# Hardware5button.net
KiCad netlist of a schematic drawn in Altium Designer
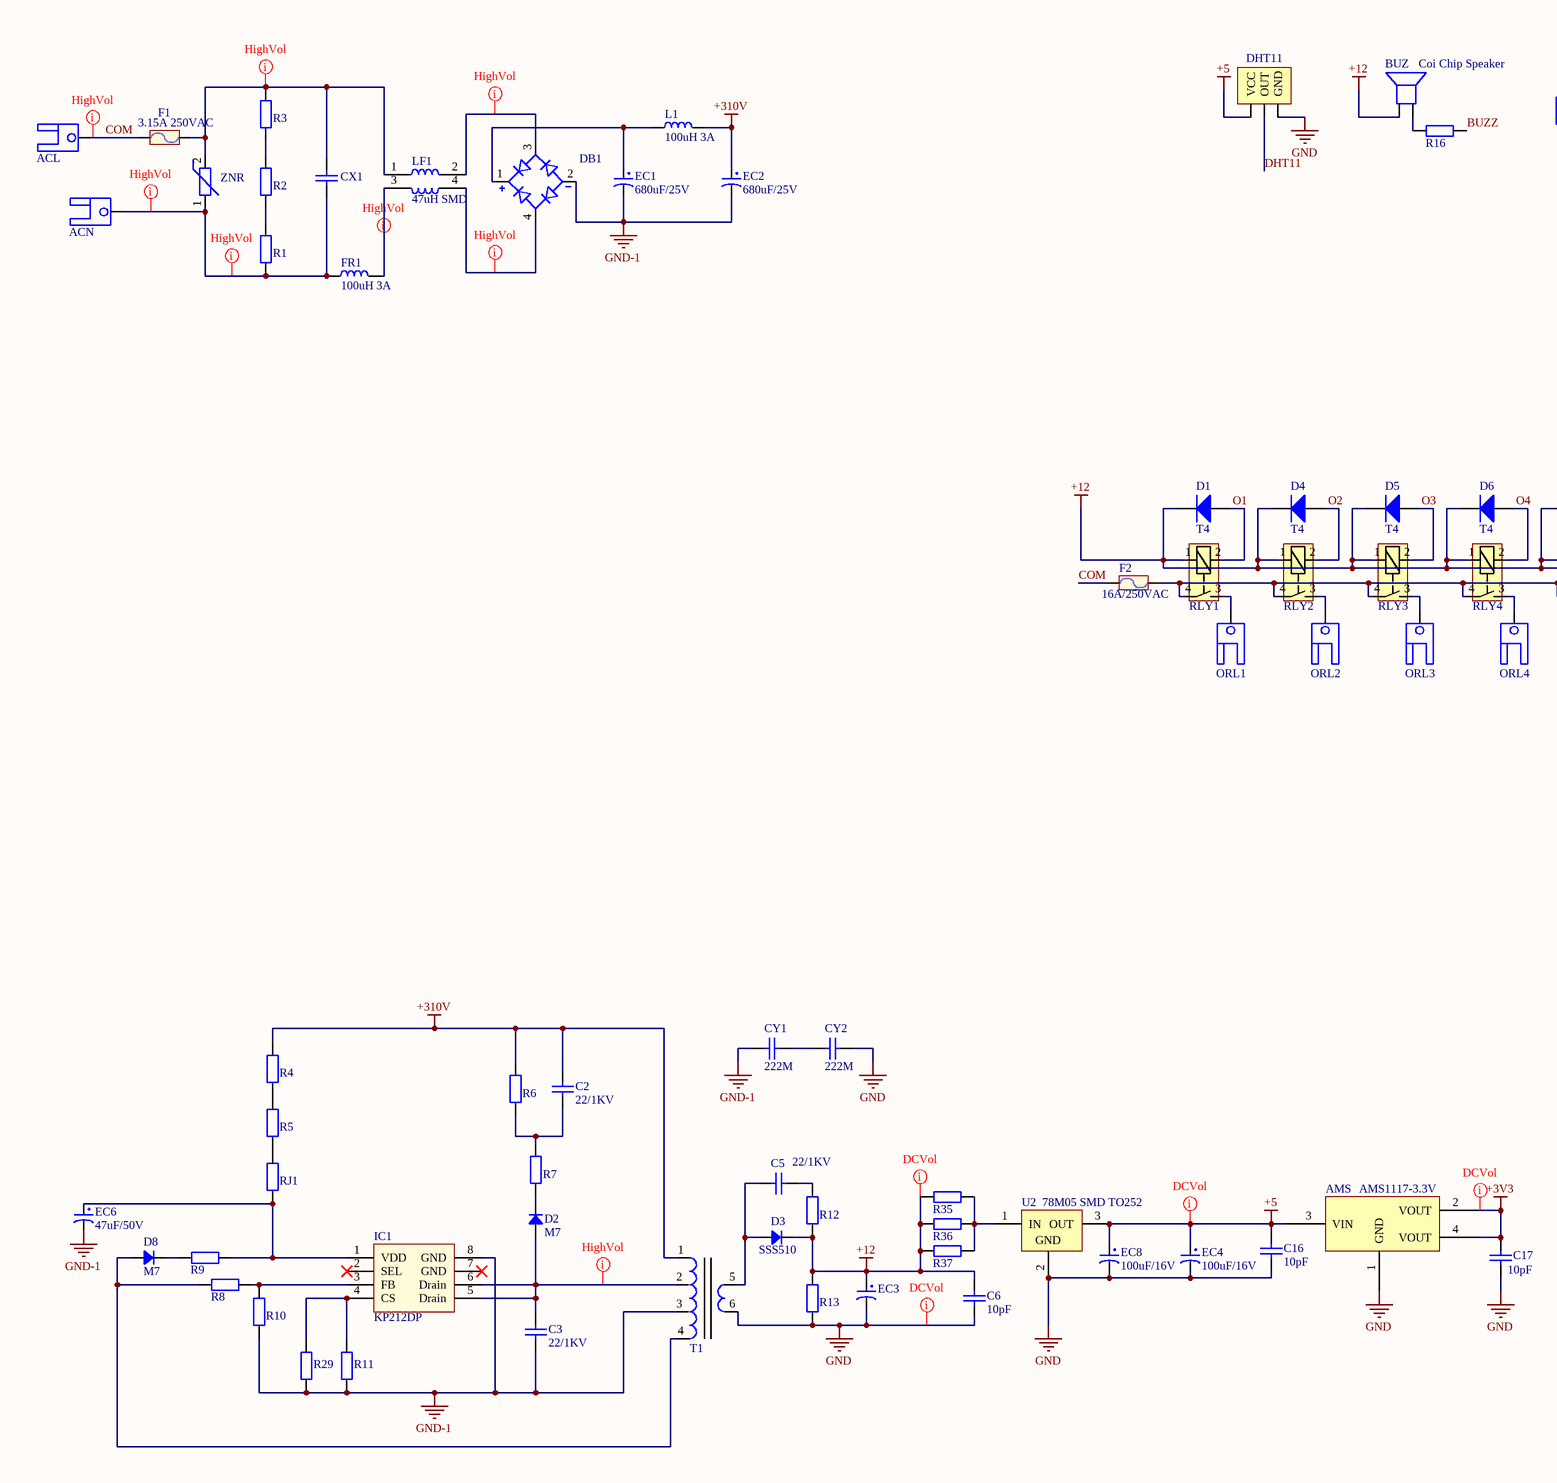
[diagram p0: Hardware5button.SchDoc, left]
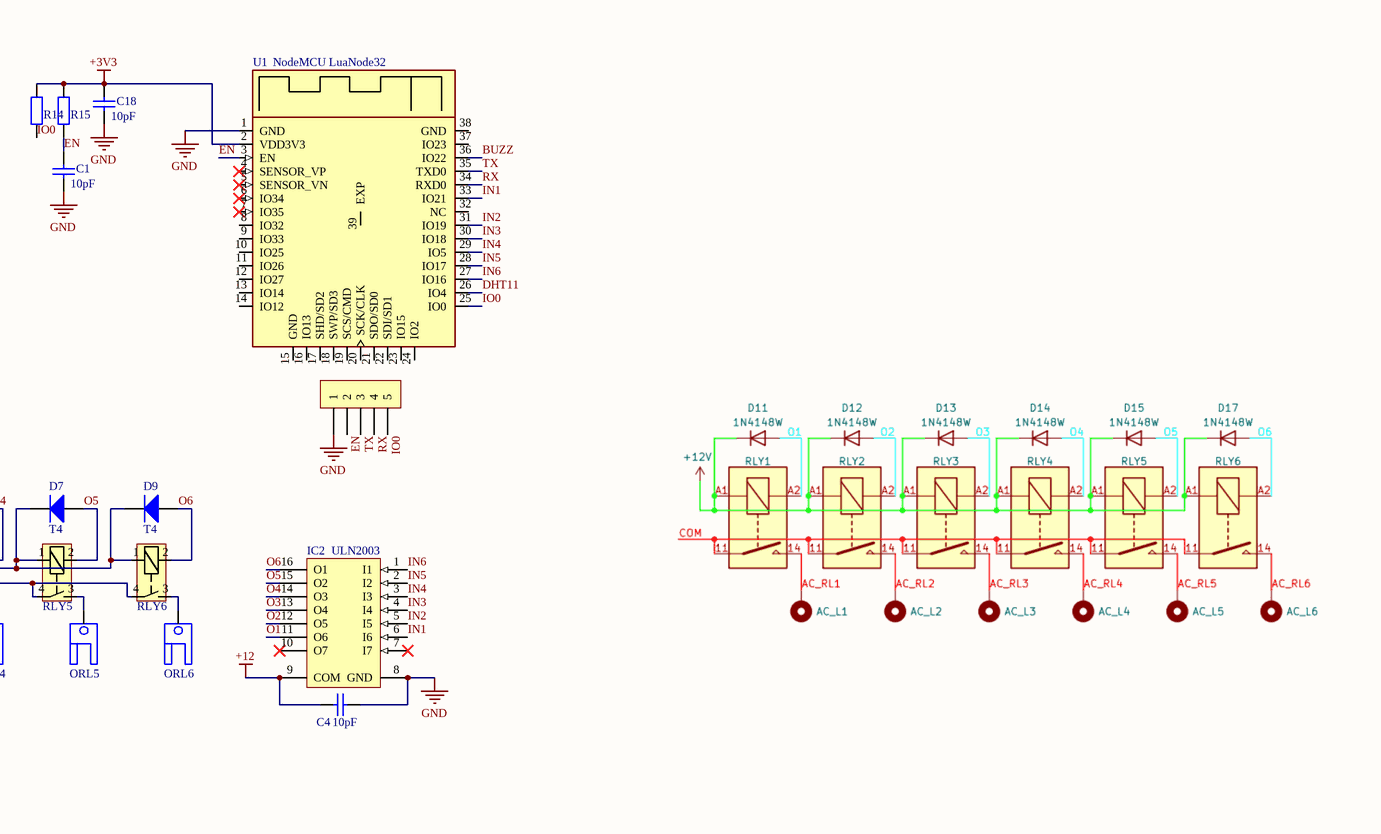
[diagram p1: Hardware5button.SchDoc, right]

(export (version "E")
  (design (tool "Eeschema 10.0.6"))
  (components
    (comp (ref "ACL")
      (value "1217861-1")
      (footprint "CON1_P192_70D137_TH_ST")
      (description "1 Pins, 1 Row 256mil Pitch, Straight, Male")
      (fields
        (field (name "MANUFACTURER") "TE Connectivity")
        (field (name "MATING PART NUMBER") "2-520183-2")
      )
      (libsource (lib "SF16_POWER") (part "CON-PLG-SPADE_1X1-256-ST-TH"))
    )
    (comp (ref "ACN")
      (value "1217861-1")
      (footprint "CON1_P192_70D137_TH_ST")
      (description "1 Pins, 1 Row 256mil Pitch, Straight, Male")
      (fields
        (field (name "MANUFACTURER") "TE Connectivity")
        (field (name "MATING PART NUMBER") "2-520183-2")
      )
      (libsource (lib "SF16_POWER") (part "CON-PLG-SPADE_1X1-256-ST-TH"))
    )
    (comp (ref "AMS")
      (value "AMS1117-3.3V")
      (footprint "SOT223")
      (description "Dán")
      (libsource (lib "SF16_POWER") (part "AMS1117 SMD"))
    )
    (comp (ref "BUZ")
      (value "Coi Chip Speaker")
      (footprint "Coi 14mm")
      (description "Cắm")
      (libsource (lib "SF16_POWER") (part "Coi 14mm"))
    )
    (comp (ref "C1")
      (value "10pF")
      (footprint "tu 0805")
      (description "Dán")
      (libsource (lib "SF16_POWER") (part "Tu 0805 10pF 50V 10%"))
    )
    (comp (ref "C2")
      (value "22/1KV")
      (footprint "TU GOM CAO AP")
      (description "Cắm")
      (libsource (lib "SF16_POWER") (part "Tu gom CAO AP"))
    )
    (comp (ref "C3")
      (value "22/1KV")
      (footprint "TU GOM CAO AP")
      (description "Cắm")
      (libsource (lib "SF16_POWER") (part "Tu gom CAO AP"))
    )
    (comp (ref "C4")
      (value "10pF")
      (footprint "tu 0805")
      (description "Dán")
      (libsource (lib "SF16_POWER") (part "Tu 0805 10pF 50V 10%"))
    )
    (comp (ref "C5")
      (value "22/1KV")
      (footprint "TU GOM CAO AP")
      (description "Cắm")
      (libsource (lib "SF16_POWER") (part "Tu gom CAO AP"))
    )
    (comp (ref "C6")
      (value "10pF")
      (footprint "tu 0805")
      (description "Dán")
      (libsource (lib "SF16_POWER") (part "Tu 0805 10pF 50V 10%"))
    )
    (comp (ref "C16")
      (value "10pF")
      (footprint "tu 0805")
      (description "Dán")
      (libsource (lib "SF16_POWER") (part "Tu 0805 10pF 50V 10%"))
    )
    (comp (ref "C17")
      (value "10pF")
      (footprint "tu 0805")
      (description "Dán")
      (libsource (lib "SF16_POWER") (part "Tu 0805 10pF 50V 10%"))
    )
    (comp (ref "C18")
      (value "10pF")
      (footprint "tu 0805")
      (description "Dán")
      (libsource (lib "SF16_POWER") (part "Tu 0805 10pF 50V 10%"))
    )
    (comp (ref "CX1")
      (value "0.1")
      (footprint "Tu vuong 10mm")
      (description "Cắm")
      (libsource (lib "SF16_POWER") (part "Tu MKP X2 0.1uF 275VAC 10MM"))
    )
    (comp (ref "CY1")
      (value "222M")
      (footprint "TU GOM CAO AP 222M")
      (description "Cắm")
      (libsource (lib "SF16_POWER") (part "Tu gom CAO AP 222M"))
    )
    (comp (ref "CY2")
      (value "222M")
      (footprint "TU GOM CAO AP 222M")
      (description "Cắm")
      (libsource (lib "SF16_POWER") (part "Tu gom CAO AP 222M"))
    )
    (comp (ref "D1")
      (value "T4")
      (footprint "DIODE SOD-123")
      (description "Dán")
      (libsource (lib "SF16_POWER") (part "Diode S4"))
    )
    (comp (ref "D2")
      (value "M7")
      (footprint "DIODE SMA")
      (description "Dán")
      (libsource (lib "SF16_POWER") (part "Diode M7 1N4007 SMD 1A 1000V"))
    )
    (comp (ref "D3")
      (value "SSS510")
      (footprint "DIODE SMA")
      (description "Dán")
      (libsource (lib "SF16_POWER") (part "Diode M7 1N4007 SMD 1A 1000V"))
    )
    (comp (ref "D4")
      (value "T4")
      (footprint "DIODE SOD-123")
      (description "Dán")
      (libsource (lib "SF16_POWER") (part "Diode S4"))
    )
    (comp (ref "D5")
      (value "T4")
      (footprint "DIODE SOD-123")
      (description "Dán")
      (libsource (lib "SF16_POWER") (part "Diode S4"))
    )
    (comp (ref "D6")
      (value "T4")
      (footprint "DIODE SOD-123")
      (description "Dán")
      (libsource (lib "SF16_POWER") (part "Diode S4"))
    )
    (comp (ref "D7")
      (value "T4")
      (footprint "DIODE SOD-123")
      (description "Dán")
      (libsource (lib "SF16_POWER") (part "Diode S4"))
    )
    (comp (ref "D8")
      (value "M7")
      (footprint "DIODE SMA")
      (description "Dán")
      (libsource (lib "SF16_POWER") (part "Diode M7 1N4007 SMD 1A 1000V"))
    )
    (comp (ref "D9")
      (value "T4")
      (footprint "DIODE SOD-123")
      (description "Dán")
      (libsource (lib "SF16_POWER") (part "Diode S4"))
    )
    (comp (ref "DB1")
      (value "MLB10S")
      (footprint "MBLS-1")
      (description "DÁN")
      (libsource (lib "SF16_POWER") (part "diode cau MLB10S"))
    )
    (comp (ref "DHT11")
      (value "1x3 2.54")
      (footprint "DHT11")
      (description "Cắm")
      (libsource (lib "SF16_POWER") (part "DHT11 Module"))
    )
    (comp (ref "EC1")
      (value "680uF/25V")
      (footprint "tu hoa 10mm")
      (description "Cắm")
      (libsource (lib "SF16_POWER") (part "Tu Hoa 6.8uF 400V 10x17"))
    )
    (comp (ref "EC2")
      (value "680uF/25V")
      (footprint "tu hoa 10mm")
      (description "Cắm")
      (libsource (lib "SF16_POWER") (part "Tu Hoa 6.8uF 400V 10x17"))
    )
    (comp (ref "EC3")
      (value "10UF/400V")
      (footprint "tu hoa 10mm")
      (description "Cắm")
      (libsource (lib "SF16_POWER") (part "Tu Hoa 1000uF 10V 10x12"))
    )
    (comp (ref "EC4")
      (value "100uF/16V")
      (footprint "tu hoa 5mm")
      (description "Cắm")
      (libsource (lib "SF16_POWER") (part "Tu Hoa 330uF 10V 6x11"))
    )
    (comp (ref "EC6")
      (value "47uF/50V")
      (footprint "tu hoa 5mm")
      (description "Cắm")
      (libsource (lib "SF16_POWER") (part "Tu Hoa 47uF 16V 5x10"))
    )
    (comp (ref "EC8")
      (value "100uF/16V")
      (footprint "tu hoa 5mm")
      (description "Cắm")
      (libsource (lib "SF16_POWER") (part "Tu Hoa 330uF 10V 6x11"))
    )
    (comp (ref "F1")
      (value "3.15A 250VAC")
      (footprint "Cau chi 2A 250V T2A250V")
      (description "Cắm")
      (libsource (lib "SF16_POWER") (part "Cau chi 2A 250V T2A250V_1"))
    )
    (comp (ref "F2")
      (value "16A/250VAC")
      (footprint "Cau Chi 250V")
      (description "Cắm")
      (libsource (lib "SF16_POWER") (part "Cau chi 16A 250V"))
    )
    (comp (ref "FR1")
      (value "100uH 3A")
      (footprint "CUON CAM - duplicate")
      (description "Cắm")
      (libsource (lib "SF16_POWER") (part "CUON CAM VACH DUNG"))
    )
    (comp (ref "H1")
      (value "Header 5P 2.54 DT")
      (footprint "XH2.54M-5")
      (description "Cắm")
      (libsource (lib "SF16_POWER") (part "Header 5P 2.54 DT"))
    )
    (comp (ref "IC1")
      (value "KP212DP")
      (footprint "DIP8")
      (description "Cắm")
      (libsource (lib "SF16_POWER") (part "KP212"))
    )
    (comp (ref "IC2")
      (value "ULN2003")
      (footprint "SOP 16")
      (description "Dán")
      (libsource (lib "SF16_POWER") (part "ULN2003A SMD"))
    )
    (comp (ref "L1")
      (value "100uH 3A")
      (footprint "CUON CAM - duplicate")
      (description "Cắm")
      (libsource (lib "SF16_POWER") (part "CUON CAM VACH DUNG"))
    )
    (comp (ref "LF1")
      (value "47uH SMD")
      (footprint "Cuon Cam AC-AC")
      (description "Cắm")
      (libsource (lib "SF16_POWER") (part "CUON CAM AC_AC"))
    )
    (comp (ref "ORL1")
      (value "1217861-1")
      (footprint "CON1_P192_70D137_TH_ST")
      (description "1 Pins, 1 Row 256mil Pitch, Straight, Male")
      (fields
        (field (name "MANUFACTURER") "TE Connectivity")
        (field (name "MATING PART NUMBER") "2-520183-2")
      )
      (libsource (lib "SF16_POWER") (part "CON-PLG-SPADE_1X1-256-ST-TH"))
    )
    (comp (ref "ORL2")
      (value "1217861-1")
      (footprint "CON1_P192_70D137_TH_ST")
      (description "1 Pins, 1 Row 256mil Pitch, Straight, Male")
      (fields
        (field (name "MANUFACTURER") "TE Connectivity")
        (field (name "MATING PART NUMBER") "2-520183-2")
      )
      (libsource (lib "SF16_POWER") (part "CON-PLG-SPADE_1X1-256-ST-TH"))
    )
    (comp (ref "ORL3")
      (value "1217861-1")
      (footprint "CON1_P192_70D137_TH_ST")
      (description "1 Pins, 1 Row 256mil Pitch, Straight, Male")
      (fields
        (field (name "MANUFACTURER") "TE Connectivity")
        (field (name "MATING PART NUMBER") "2-520183-2")
      )
      (libsource (lib "SF16_POWER") (part "CON-PLG-SPADE_1X1-256-ST-TH"))
    )
    (comp (ref "ORL4")
      (value "1217861-1")
      (footprint "CON1_P192_70D137_TH_ST")
      (description "1 Pins, 1 Row 256mil Pitch, Straight, Male")
      (fields
        (field (name "MANUFACTURER") "TE Connectivity")
        (field (name "MATING PART NUMBER") "2-520183-2")
      )
      (libsource (lib "SF16_POWER") (part "CON-PLG-SPADE_1X1-256-ST-TH"))
    )
    (comp (ref "ORL5")
      (value "1217861-1")
      (footprint "CON1_P192_70D137_TH_ST")
      (description "1 Pins, 1 Row 256mil Pitch, Straight, Male")
      (fields
        (field (name "MANUFACTURER") "TE Connectivity")
        (field (name "MATING PART NUMBER") "2-520183-2")
      )
      (libsource (lib "SF16_POWER") (part "CON-PLG-SPADE_1X1-256-ST-TH"))
    )
    (comp (ref "ORL6")
      (value "1217861-1")
      (footprint "CON1_P192_70D137_TH_ST")
      (description "1 Pins, 1 Row 256mil Pitch, Straight, Male")
      (fields
        (field (name "MANUFACTURER") "TE Connectivity")
        (field (name "MATING PART NUMBER") "2-520183-2")
      )
      (libsource (lib "SF16_POWER") (part "CON-PLG-SPADE_1X1-256-ST-TH"))
    )
    (comp (ref "R1")
      (value "0.68R")
      (footprint "tro smd 1206")
      (description "Dán")
      (libsource (lib "SF16_POWER") (part "Tro 1206"))
    )
    (comp (ref "R2")
      (value "0.68R")
      (footprint "tro smd 1206")
      (description "Dán")
      (libsource (lib "SF16_POWER") (part "Tro 1206"))
    )
    (comp (ref "R3")
      (value "0.68R")
      (footprint "tro smd 1206")
      (description "Dán")
      (libsource (lib "SF16_POWER") (part "Tro 1206"))
    )
    (comp (ref "R4")
      (value "0.68R")
      (footprint "tro smd 1206")
      (description "Dán")
      (libsource (lib "SF16_POWER") (part "Tro 1206"))
    )
    (comp (ref "R5")
      (value "0.68R")
      (footprint "tro smd 1206")
      (description "Dán")
      (libsource (lib "SF16_POWER") (part "Tro 1206"))
    )
    (comp (ref "R6")
      (value "0.68R")
      (footprint "tro smd 1206")
      (description "Dán")
      (libsource (lib "SF16_POWER") (part "Tro 1206"))
    )
    (comp (ref "R7")
      (value "0.68R")
      (footprint "tro smd 1206")
      (description "Dán")
      (libsource (lib "SF16_POWER") (part "Tro 1206"))
    )
    (comp (ref "R8")
      (value "0.22R")
      (footprint "tro smd 0805")
      (description "Dán")
      (libsource (lib "SF16_POWER") (part "Tro 0805"))
    )
    (comp (ref "R9")
      (value "0.68R")
      (footprint "tro smd 1206")
      (description "Dán")
      (libsource (lib "SF16_POWER") (part "Tro 1206"))
    )
    (comp (ref "R10")
      (value "0.22R")
      (footprint "tro smd 0805")
      (description "Dán")
      (libsource (lib "SF16_POWER") (part "Tro 0805"))
    )
    (comp (ref "R11")
      (value "0.68R")
      (footprint "tro smd 1206")
      (description "Dán")
      (libsource (lib "SF16_POWER") (part "Tro 1206"))
    )
    (comp (ref "R12")
      (value "0.68R")
      (footprint "tro smd 1206")
      (description "Dán")
      (libsource (lib "SF16_POWER") (part "Tro 1206"))
    )
    (comp (ref "R13")
      (value "0.22R")
      (footprint "tro smd 0805")
      (description "Dán")
      (libsource (lib "SF16_POWER") (part "Tro 0805"))
    )
    (comp (ref "R14")
      (value "0.22R")
      (footprint "tro smd 0805")
      (description "Dán")
      (libsource (lib "SF16_POWER") (part "Tro 0805"))
    )
    (comp (ref "R15")
      (value "0.22R")
      (footprint "tro smd 0805")
      (description "Dán")
      (libsource (lib "SF16_POWER") (part "Tro 0805"))
    )
    (comp (ref "R16")
      (value "0.22R")
      (footprint "tro smd 0805")
      (description "Dán")
      (libsource (lib "SF16_POWER") (part "Tro 0805"))
    )
    (comp (ref "R29")
      (value "0.68R")
      (footprint "tro smd 1206")
      (description "Dán")
      (libsource (lib "SF16_POWER") (part "Tro 1206"))
    )
    (comp (ref "R35")
      (value "0.68R")
      (footprint "tro smd 1206")
      (description "Dán")
      (libsource (lib "SF16_POWER") (part "Tro 1206"))
    )
    (comp (ref "R36")
      (value "0.68R")
      (footprint "tro smd 1206")
      (description "Dán")
      (libsource (lib "SF16_POWER") (part "Tro 1206"))
    )
    (comp (ref "R37")
      (value "0.68R")
      (footprint "tro smd 1206")
      (description "Dán")
      (libsource (lib "SF16_POWER") (part "Tro 1206"))
    )
    (comp (ref "RJ1")
      (value "0.68R")
      (footprint "tro smd 1206")
      (description "Dán")
      (libsource (lib "SF16_POWER") (part "Tro 1206"))
    )
    (comp (ref "RLY1")
      (value "Relay JZC-8F-1H")
      (footprint "Relay 4 chan JZC-8F")
      (description "Cắm")
      (libsource (lib "SF16_POWER") (part "Relay 4 chan JZC-8F-1H"))
    )
    (comp (ref "RLY2")
      (value "Relay JZC-8F-1H")
      (footprint "Relay 4 chan JZC-8F")
      (description "Cắm")
      (libsource (lib "SF16_POWER") (part "Relay 4 chan JZC-8F-1H"))
    )
    (comp (ref "RLY3")
      (value "Relay JZC-8F-1H")
      (footprint "Relay 4 chan JZC-8F")
      (description "Cắm")
      (libsource (lib "SF16_POWER") (part "Relay 4 chan JZC-8F-1H"))
    )
    (comp (ref "RLY4")
      (value "Relay JZC-8F-1H")
      (footprint "Relay 4 chan JZC-8F")
      (description "Cắm")
      (libsource (lib "SF16_POWER") (part "Relay 4 chan JZC-8F-1H"))
    )
    (comp (ref "RLY5")
      (value "Relay JZC-8F-1H")
      (footprint "Relay 4 chan JZC-8F")
      (description "Cắm")
      (libsource (lib "SF16_POWER") (part "Relay 4 chan JZC-8F-1H"))
    )
    (comp (ref "RLY6")
      (value "Relay JZC-8F-1H")
      (footprint "Relay 4 chan JZC-8F")
      (description "Cắm")
      (libsource (lib "SF16_POWER") (part "Relay 4 chan JZC-8F-1H"))
    )
    (comp (ref "T1")
      (value "Bien ap")
      (footprint "BIEN AP EE1610-12V1.1A")
      (description "Cắm")
      (libsource (lib "SF16_POWER") (part "Bien ap"))
    )
    (comp (ref "U1")
      (value "NodeMCU LuaNode32")
      (footprint "ESP32-WROOM-32D")
      (description "Dán")
      (libsource (lib "SF16_POWER") (part "ESP32 WROOM 32"))
    )
    (comp (ref "U2")
      (value "78M05 SMD TO252")
      (footprint "TO252")
      (description "Dán")
      (libsource (lib "SF16_POWER") (part "78M05 SMD TO252"))
    )
    (comp (ref "ZNR")
      (value "MOV-07D471KTR")
      (footprint "Tu MOV - duplicate")
      (description "Cam")
      (fields
        (field (name "OCTOPART") "https://octopart.com/mov-07d471ktr-bourns-19184728")
        (field (name "MANUFACTURER") "Bourns Inc.")
      )
      (libsource (lib "SF16_POWER") (part "Varistor 10D471K 470V"))
    )
  )
  (nets
    (net (code "1") (name "+3V3") (class "Default")
      (node (ref "AMS") (pin "2") (pinfunction "VOUT_2") (pintype "passive"))
      (node (ref "AMS") (pin "4") (pinfunction "VOUT_4") (pintype "passive"))
      (node (ref "C17") (pin "1") (pinfunction "1_1") (pintype "passive"))
      (node (ref "C18") (pin "1") (pinfunction "1_1") (pintype "passive"))
      (node (ref "R14") (pin "2") (pinfunction "2_2") (pintype "passive"))
      (node (ref "R15") (pin "2") (pinfunction "2_2") (pintype "passive"))
      (node (ref "U1") (pin "2") (pinfunction "VDD3V3_2") (pintype "power_in"))
    )
    (net (code "2") (name "+5") (class "Default")
      (node (ref "AMS") (pin "3") (pinfunction "VIN_3") (pintype "passive"))
      (node (ref "C16") (pin "1") (pinfunction "1_1") (pintype "passive"))
      (node (ref "DHT11") (pin "1") (pinfunction "VCC_1") (pintype "passive"))
      (node (ref "EC4") (pin "1") (pinfunction "1_1") (pintype "passive"))
      (node (ref "EC8") (pin "1") (pinfunction "1_1") (pintype "passive"))
      (node (ref "U2") (pin "3") (pinfunction "OUT_3") (pintype "power_in"))
    )
    (net (code "3") (name "+12") (class "Default")
      (node (ref "BUZ") (pin "1") (pinfunction "1_1") (pintype "passive"))
      (node (ref "C4") (pin "1") (pinfunction "1_1") (pintype "passive"))
      (node (ref "C6") (pin "1") (pinfunction "1_1") (pintype "passive"))
      (node (ref "D1") (pin "2") (pinfunction "K_2") (pintype "passive"))
      (node (ref "D3") (pin "2") (pinfunction "K_2") (pintype "passive"))
      (node (ref "D4") (pin "2") (pinfunction "K_2") (pintype "passive"))
      (node (ref "D5") (pin "2") (pinfunction "K_2") (pintype "passive"))
      (node (ref "D6") (pin "2") (pinfunction "K_2") (pintype "passive"))
      (node (ref "D7") (pin "2") (pinfunction "K_2") (pintype "passive"))
      (node (ref "D9") (pin "2") (pinfunction "K_2") (pintype "passive"))
      (node (ref "EC3") (pin "1") (pinfunction "1_1") (pintype "passive"))
      (node (ref "IC2") (pin "9") (pinfunction "COM_9") (pintype "passive"))
      (node (ref "R12") (pin "1") (pinfunction "1_1") (pintype "passive"))
      (node (ref "R13") (pin "2") (pinfunction "2_2") (pintype "passive"))
      (node (ref "R35") (pin "2") (pinfunction "2_2") (pintype "passive"))
      (node (ref "R36") (pin "2") (pinfunction "2_2") (pintype "passive"))
      (node (ref "R37") (pin "2") (pinfunction "2_2") (pintype "passive"))
      (node (ref "RLY1") (pin "1") (pintype "passive"))
      (node (ref "RLY2") (pin "1") (pintype "passive"))
      (node (ref "RLY3") (pin "1") (pintype "passive"))
      (node (ref "RLY4") (pin "1") (pintype "passive"))
      (node (ref "RLY5") (pin "1") (pintype "passive"))
      (node (ref "RLY6") (pin "1") (pintype "passive"))
    )
    (net (code "4") (name "+310V") (class "Default")
      (node (ref "C2") (pin "1") (pinfunction "1_1") (pintype "passive"))
      (node (ref "EC2") (pin "1") (pinfunction "1_1") (pintype "passive"))
      (node (ref "L1") (pin "2") (pinfunction "2_2") (pintype "passive"))
      (node (ref "R4") (pin "2") (pinfunction "2_2") (pintype "passive"))
      (node (ref "R6") (pin "2") (pinfunction "2_2") (pintype "passive"))
      (node (ref "T1") (pin "1") (pinfunction "4_1") (pintype "passive"))
    )
    (net (code "5") (name "/BUZZ") (class "Default")
      (node (ref "R16") (pin "1") (pinfunction "1_1") (pintype "passive"))
      (node (ref "U1") (pin "36") (pinfunction "IO22_36") (pintype "bidirectional"))
    )
    (net (code "6") (name "/COM") (class "Default")
      (node (ref "ACL") (pin "1") (pinfunction "1_1") (pintype "passive"))
      (node (ref "F1") (pin "1") (pinfunction "1_1") (pintype "passive"))
      (node (ref "F2") (pin "1") (pinfunction "1_1") (pintype "passive"))
    )
    (net (code "7") (name "/DHT11") (class "Default")
      (node (ref "DHT11") (pin "2") (pinfunction "OUT_2") (pintype "passive"))
      (node (ref "U1") (pin "26") (pinfunction "IO4_26") (pintype "bidirectional"))
    )
    (net (code "8") (name "/EN") (class "Default")
      (node (ref "C1") (pin "1") (pinfunction "1_1") (pintype "passive"))
      (node (ref "H1") (pin "2") (pinfunction "2_2") (pintype "passive"))
      (node (ref "R15") (pin "1") (pinfunction "1_1") (pintype "passive"))
      (node (ref "U1") (pin "3") (pinfunction "EN_3") (pintype "input"))
    )
    (net (code "9") (name "/IN1") (class "Default")
      (node (ref "IC2") (pin "6") (pinfunction "I6_6") (pintype "input"))
      (node (ref "U1") (pin "33") (pinfunction "IO21_33") (pintype "bidirectional"))
    )
    (net (code "10") (name "/IN2") (class "Default")
      (node (ref "IC2") (pin "5") (pinfunction "I5_5") (pintype "input"))
      (node (ref "U1") (pin "31") (pinfunction "IO19_31") (pintype "bidirectional"))
    )
    (net (code "11") (name "/IN3") (class "Default")
      (node (ref "IC2") (pin "4") (pinfunction "I4_4") (pintype "input"))
      (node (ref "U1") (pin "30") (pinfunction "IO18_30") (pintype "bidirectional"))
    )
    (net (code "12") (name "/IN4") (class "Default")
      (node (ref "IC2") (pin "3") (pinfunction "I3_3") (pintype "input"))
      (node (ref "U1") (pin "29") (pinfunction "IO5_29") (pintype "bidirectional"))
    )
    (net (code "13") (name "/IN5") (class "Default")
      (node (ref "IC2") (pin "2") (pinfunction "I2_2") (pintype "input"))
      (node (ref "U1") (pin "28") (pinfunction "IO17_28") (pintype "bidirectional"))
    )
    (net (code "14") (name "/IN6") (class "Default")
      (node (ref "IC2") (pin "1") (pinfunction "I1_1") (pintype "input"))
      (node (ref "U1") (pin "27") (pinfunction "IO16_27") (pintype "bidirectional"))
    )
    (net (code "15") (name "/IO0") (class "Default")
      (node (ref "H1") (pin "5") (pinfunction "5_5") (pintype "passive"))
      (node (ref "R14") (pin "1") (pinfunction "1_1") (pintype "passive"))
      (node (ref "U1") (pin "25") (pinfunction "IO0_25") (pintype "bidirectional"))
    )
    (net (code "16") (name "/O1") (class "Default")
      (node (ref "D1") (pin "1") (pinfunction "A_1") (pintype "passive"))
      (node (ref "IC2") (pin "11") (pinfunction "O6_11") (pintype "open_collector"))
      (node (ref "RLY1") (pin "2") (pintype "passive"))
    )
    (net (code "17") (name "/O2") (class "Default")
      (node (ref "D4") (pin "1") (pinfunction "A_1") (pintype "passive"))
      (node (ref "IC2") (pin "12") (pinfunction "O5_12") (pintype "open_collector"))
      (node (ref "RLY2") (pin "2") (pintype "passive"))
    )
    (net (code "18") (name "/O3") (class "Default")
      (node (ref "D5") (pin "1") (pinfunction "A_1") (pintype "passive"))
      (node (ref "IC2") (pin "13") (pinfunction "O4_13") (pintype "open_collector"))
      (node (ref "RLY3") (pin "2") (pintype "passive"))
    )
    (net (code "19") (name "/O4") (class "Default")
      (node (ref "D6") (pin "1") (pinfunction "A_1") (pintype "passive"))
      (node (ref "IC2") (pin "14") (pinfunction "O3_14") (pintype "open_collector"))
      (node (ref "RLY4") (pin "2") (pintype "passive"))
    )
    (net (code "20") (name "/O5") (class "Default")
      (node (ref "D7") (pin "1") (pinfunction "A_1") (pintype "passive"))
      (node (ref "IC2") (pin "15") (pinfunction "O2_15") (pintype "open_collector"))
      (node (ref "RLY5") (pin "2") (pintype "passive"))
    )
    (net (code "21") (name "/O6") (class "Default")
      (node (ref "D9") (pin "1") (pinfunction "A_1") (pintype "passive"))
      (node (ref "IC2") (pin "16") (pinfunction "O1_16") (pintype "open_collector"))
      (node (ref "RLY6") (pin "2") (pintype "passive"))
    )
    (net (code "22") (name "/RX") (class "Default")
      (node (ref "H1") (pin "4") (pinfunction "4_4") (pintype "passive"))
      (node (ref "U1") (pin "34") (pinfunction "RXD0_34") (pintype "bidirectional"))
    )
    (net (code "23") (name "/TX") (class "Default")
      (node (ref "H1") (pin "3") (pinfunction "3_3") (pintype "passive"))
      (node (ref "U1") (pin "35") (pinfunction "TXD0_35") (pintype "bidirectional"))
    )
    (net (code "24") (name "GND") (class "Default")
      (node (ref "AMS") (pin "1") (pinfunction "GND_1") (pintype "passive"))
      (node (ref "C1") (pin "2") (pinfunction "2_2") (pintype "passive"))
      (node (ref "C16") (pin "2") (pinfunction "2_2") (pintype "passive"))
      (node (ref "C17") (pin "2") (pinfunction "2_2") (pintype "passive"))
      (node (ref "C18") (pin "2") (pinfunction "2_2") (pintype "passive"))
      (node (ref "C4") (pin "2") (pinfunction "2_2") (pintype "passive"))
      (node (ref "C6") (pin "2") (pinfunction "2_2") (pintype "passive"))
      (node (ref "CY2") (pin "1") (pinfunction "1_1") (pintype "passive"))
      (node (ref "DHT11") (pin "3") (pinfunction "GND_3") (pintype "passive"))
      (node (ref "EC3") (pin "2") (pinfunction "2_2") (pintype "passive"))
      (node (ref "EC4") (pin "2") (pinfunction "2_2") (pintype "passive"))
      (node (ref "EC8") (pin "2") (pinfunction "2_2") (pintype "passive"))
      (node (ref "H1") (pin "1") (pinfunction "1_1") (pintype "passive"))
      (node (ref "IC2") (pin "8") (pinfunction "GND_8") (pintype "power_in"))
      (node (ref "R13") (pin "1") (pinfunction "1_1") (pintype "passive"))
      (node (ref "T1") (pin "6") (pinfunction "5_6") (pintype "passive"))
      (node (ref "U1") (pin "1") (pinfunction "GND_1") (pintype "power_in"))
      (node (ref "U2") (pin "2") (pinfunction "GND_2") (pintype "power_in"))
    )
    (net (code "25") (name "GND-1") (class "Default")
      (node (ref "C3") (pin "2") (pinfunction "2_2") (pintype "passive"))
      (node (ref "CY1") (pin "2") (pinfunction "2_2") (pintype "passive"))
      (node (ref "DB1") (pin "2") (pinfunction "NEG_2") (pintype "passive"))
      (node (ref "EC1") (pin "2") (pinfunction "2_2") (pintype "passive"))
      (node (ref "EC2") (pin "2") (pinfunction "2_2") (pintype "passive"))
      (node (ref "EC6") (pin "2") (pinfunction "2_2") (pintype "passive"))
      (node (ref "IC1") (pin "8") (pinfunction "GND_8") (pintype "power_in"))
      (node (ref "R10") (pin "1") (pinfunction "1_1") (pintype "passive"))
      (node (ref "R11") (pin "1") (pinfunction "1_1") (pintype "passive"))
      (node (ref "R29") (pin "1") (pinfunction "1_1") (pintype "passive"))
      (node (ref "T1") (pin "3") (pinfunction "4_3") (pintype "passive"))
    )
    (net (code "26") (name "Net-(ACN-Pad1)") (class "Default")
      (node (ref "ACN") (pin "1") (pinfunction "1_1") (pintype "passive"))
      (node (ref "CX1") (pin "2") (pinfunction "2_2") (pintype "passive"))
      (node (ref "FR1") (pin "1") (pinfunction "1_1") (pintype "passive"))
      (node (ref "R1") (pin "1") (pinfunction "1_1") (pintype "passive"))
      (node (ref "ZNR") (pin "1") (pinfunction "1_1") (pintype "passive"))
    )
    (net (code "27") (name "Net-(BUZ-Pad2)") (class "Default")
      (node (ref "BUZ") (pin "2") (pinfunction "2_2") (pintype "passive"))
      (node (ref "R16") (pin "2") (pinfunction "2_2") (pintype "passive"))
    )
    (net (code "28") (name "Net-(C2-Pad2)") (class "Default")
      (node (ref "C2") (pin "2") (pinfunction "2_2") (pintype "passive"))
      (node (ref "R6") (pin "1") (pinfunction "1_1") (pintype "passive"))
      (node (ref "R7") (pin "2") (pinfunction "2_2") (pintype "passive"))
    )
    (net (code "29") (name "Net-(C5-Pad2)") (class "Default")
      (node (ref "C5") (pin "2") (pinfunction "2_2") (pintype "passive"))
      (node (ref "R12") (pin "2") (pinfunction "2_2") (pintype "passive"))
    )
    (net (code "30") (name "Net-(CX1-Pad1)") (class "Default")
      (node (ref "CX1") (pin "1") (pinfunction "1_1") (pintype "passive"))
      (node (ref "F1") (pin "2") (pinfunction "2_2") (pintype "passive"))
      (node (ref "LF1") (pin "1") (pinfunction "1_1") (pintype "passive"))
      (node (ref "R3") (pin "2") (pinfunction "2_2") (pintype "passive"))
      (node (ref "ZNR") (pin "2") (pinfunction "2_2") (pintype "passive"))
    )
    (net (code "31") (name "Net-(CY1-Pad1)") (class "Default")
      (node (ref "CY1") (pin "1") (pinfunction "1_1") (pintype "passive"))
      (node (ref "CY2") (pin "2") (pinfunction "2_2") (pintype "passive"))
    )
    (net (code "32") (name "Net-(D2-A)") (class "Default")
      (node (ref "C3") (pin "1") (pinfunction "1_1") (pintype "passive"))
      (node (ref "D2") (pin "1") (pinfunction "A_1") (pintype "passive"))
      (node (ref "IC1") (pin "5") (pinfunction "Drain_5") (pintype "passive"))
      (node (ref "IC1") (pin "6") (pinfunction "Drain_6") (pintype "passive"))
      (node (ref "T1") (pin "2") (pinfunction "4_2") (pintype "passive"))
    )
    (net (code "33") (name "Net-(D2-K)") (class "Default")
      (node (ref "D2") (pin "2") (pinfunction "K_2") (pintype "passive"))
      (node (ref "R7") (pin "1") (pinfunction "1_1") (pintype "passive"))
    )
    (net (code "34") (name "Net-(D3-A)") (class "Default")
      (node (ref "C5") (pin "1") (pinfunction "1_1") (pintype "passive"))
      (node (ref "D3") (pin "1") (pinfunction "A_1") (pintype "passive"))
      (node (ref "T1") (pin "5") (pinfunction "4_5") (pintype "passive"))
    )
    (net (code "35") (name "Net-(D8-A)") (class "Default")
      (node (ref "D8") (pin "1") (pinfunction "A_1") (pintype "passive"))
      (node (ref "R8") (pin "1") (pinfunction "1_1") (pintype "passive"))
      (node (ref "T1") (pin "4") (pinfunction "4_4") (pintype "passive"))
    )
    (net (code "36") (name "Net-(D8-K)") (class "Default")
      (node (ref "D8") (pin "2") (pinfunction "K_2") (pintype "passive"))
      (node (ref "R9") (pin "2") (pinfunction "2_2") (pintype "passive"))
    )
    (net (code "37") (name "Net-(DB1-AC1)") (class "Default")
      (node (ref "DB1") (pin "4") (pinfunction "AC1_4") (pintype "passive"))
      (node (ref "LF1") (pin "4") (pinfunction "4_4") (pintype "passive"))
    )
    (net (code "38") (name "Net-(DB1-AC2)") (class "Default")
      (node (ref "DB1") (pin "3") (pinfunction "AC2_3") (pintype "passive"))
      (node (ref "LF1") (pin "2") (pinfunction "2_2") (pintype "passive"))
    )
    (net (code "39") (name "Net-(DB1-POS)") (class "Default")
      (node (ref "DB1") (pin "1") (pinfunction "POS_1") (pintype "passive"))
      (node (ref "EC1") (pin "1") (pinfunction "1_1") (pintype "passive"))
      (node (ref "L1") (pin "1") (pinfunction "1_1") (pintype "passive"))
    )
    (net (code "40") (name "Net-(F2-Pad2)") (class "Default")
      (node (ref "F2") (pin "2") (pinfunction "2_2") (pintype "passive"))
      (node (ref "RLY1") (pin "4") (pinfunction "AC/DC_4") (pintype "passive"))
      (node (ref "RLY2") (pin "4") (pinfunction "AC/DC_4") (pintype "passive"))
      (node (ref "RLY3") (pin "4") (pinfunction "AC/DC_4") (pintype "passive"))
      (node (ref "RLY4") (pin "4") (pinfunction "AC/DC_4") (pintype "passive"))
      (node (ref "RLY5") (pin "4") (pinfunction "AC/DC_4") (pintype "passive"))
      (node (ref "RLY6") (pin "4") (pinfunction "AC/DC_4") (pintype "passive"))
    )
    (net (code "41") (name "Net-(FR1-Pad2)") (class "Default")
      (node (ref "FR1") (pin "2") (pinfunction "2_2") (pintype "passive"))
      (node (ref "LF1") (pin "3") (pinfunction "3_3") (pintype "passive"))
    )
    (net (code "42") (name "Net-(IC1-CS)") (class "Default")
      (node (ref "IC1") (pin "4") (pinfunction "CS_4") (pintype "power_in"))
      (node (ref "R11") (pin "2") (pinfunction "2_2") (pintype "passive"))
      (node (ref "R29") (pin "2") (pinfunction "2_2") (pintype "passive"))
    )
    (net (code "43") (name "Net-(IC1-FB)") (class "Default")
      (node (ref "IC1") (pin "3") (pinfunction "FB_3") (pintype "passive"))
      (node (ref "R10") (pin "2") (pinfunction "2_2") (pintype "passive"))
      (node (ref "R8") (pin "2") (pinfunction "2_2") (pintype "passive"))
    )
    (net (code "44") (name "Net-(IC1-VDD)") (class "Default")
      (node (ref "EC6") (pin "1") (pinfunction "1_1") (pintype "passive"))
      (node (ref "IC1") (pin "1") (pinfunction "VDD_1") (pintype "passive"))
      (node (ref "R9") (pin "1") (pinfunction "1_1") (pintype "passive"))
      (node (ref "RJ1") (pin "1") (pinfunction "1_1") (pintype "passive"))
    )
    (net (code "45") (name "Net-(ORL1-Pad1)") (class "Default")
      (node (ref "ORL1") (pin "1") (pinfunction "1_1") (pintype "passive"))
      (node (ref "RLY1") (pin "3") (pinfunction "AC/DC_3") (pintype "passive"))
    )
    (net (code "46") (name "Net-(ORL2-Pad1)") (class "Default")
      (node (ref "ORL2") (pin "1") (pinfunction "1_1") (pintype "passive"))
      (node (ref "RLY2") (pin "3") (pinfunction "AC/DC_3") (pintype "passive"))
    )
    (net (code "47") (name "Net-(ORL3-Pad1)") (class "Default")
      (node (ref "ORL3") (pin "1") (pinfunction "1_1") (pintype "passive"))
      (node (ref "RLY3") (pin "3") (pinfunction "AC/DC_3") (pintype "passive"))
    )
    (net (code "48") (name "Net-(ORL4-Pad1)") (class "Default")
      (node (ref "ORL4") (pin "1") (pinfunction "1_1") (pintype "passive"))
      (node (ref "RLY4") (pin "3") (pinfunction "AC/DC_3") (pintype "passive"))
    )
    (net (code "49") (name "Net-(ORL5-Pad1)") (class "Default")
      (node (ref "ORL5") (pin "1") (pinfunction "1_1") (pintype "passive"))
      (node (ref "RLY5") (pin "3") (pinfunction "AC/DC_3") (pintype "passive"))
    )
    (net (code "50") (name "Net-(ORL6-Pad1)") (class "Default")
      (node (ref "ORL6") (pin "1") (pinfunction "1_1") (pintype "passive"))
      (node (ref "RLY6") (pin "3") (pinfunction "AC/DC_3") (pintype "passive"))
    )
    (net (code "51") (name "Net-(R1-Pad2)") (class "Default")
      (node (ref "R1") (pin "2") (pinfunction "2_2") (pintype "passive"))
      (node (ref "R2") (pin "1") (pinfunction "1_1") (pintype "passive"))
    )
    (net (code "52") (name "Net-(R2-Pad2)") (class "Default")
      (node (ref "R2") (pin "2") (pinfunction "2_2") (pintype "passive"))
      (node (ref "R3") (pin "1") (pinfunction "1_1") (pintype "passive"))
    )
    (net (code "53") (name "Net-(R4-Pad1)") (class "Default")
      (node (ref "R4") (pin "1") (pinfunction "1_1") (pintype "passive"))
      (node (ref "R5") (pin "2") (pinfunction "2_2") (pintype "passive"))
    )
    (net (code "54") (name "Net-(R5-Pad1)") (class "Default")
      (node (ref "R5") (pin "1") (pinfunction "1_1") (pintype "passive"))
      (node (ref "RJ1") (pin "2") (pinfunction "2_2") (pintype "passive"))
    )
    (net (code "55") (name "Net-(U2-IN)") (class "Default")
      (node (ref "R35") (pin "1") (pinfunction "1_1") (pintype "passive"))
      (node (ref "R36") (pin "1") (pinfunction "1_1") (pintype "passive"))
      (node (ref "R37") (pin "1") (pinfunction "1_1") (pintype "passive"))
      (node (ref "U2") (pin "1") (pinfunction "IN_1") (pintype "power_in"))
    )
    (net (code "56") (name "unconnected-(IC1-GND-Pad7)") (class "Default")
      (node (ref "IC1") (pin "7") (pinfunction "GND_7") (pintype "passive+no_connect"))
    )
    (net (code "57") (name "unconnected-(IC1-SEL-Pad2)") (class "Default")
      (node (ref "IC1") (pin "2") (pinfunction "SEL_2") (pintype "passive+no_connect"))
    )
    (net (code "58") (name "unconnected-(IC2-I7-Pad7)") (class "Default")
      (node (ref "IC2") (pin "7") (pinfunction "I7_7") (pintype "input+no_connect"))
    )
    (net (code "59") (name "unconnected-(IC2-O7-Pad10)") (class "Default")
      (node (ref "IC2") (pin "10") (pinfunction "O7_10") (pintype "open_collector+no_connect"))
    )
    (net (code "60") (name "unconnected-(U1-EXP-Pad39)") (class "Default")
      (node (ref "U1") (pin "39") (pinfunction "EXP_39") (pintype "power_in"))
    )
    (net (code "61") (name "unconnected-(U1-GND-Pad15)") (class "Default")
      (node (ref "U1") (pin "15") (pinfunction "GND_15") (pintype "power_in"))
    )
    (net (code "62") (name "unconnected-(U1-GND-Pad38)") (class "Default")
      (node (ref "U1") (pin "38") (pinfunction "GND_38") (pintype "power_in"))
    )
    (net (code "63") (name "unconnected-(U1-IO2-Pad24)") (class "Default")
      (node (ref "U1") (pin "24") (pinfunction "IO2_24") (pintype "bidirectional"))
    )
    (net (code "64") (name "unconnected-(U1-IO12-Pad14)") (class "Default")
      (node (ref "U1") (pin "14") (pinfunction "IO12_14") (pintype "bidirectional"))
    )
    (net (code "65") (name "unconnected-(U1-IO13-Pad16)") (class "Default")
      (node (ref "U1") (pin "16") (pinfunction "IO13_16") (pintype "bidirectional"))
    )
    (net (code "66") (name "unconnected-(U1-IO14-Pad13)") (class "Default")
      (node (ref "U1") (pin "13") (pinfunction "IO14_13") (pintype "bidirectional"))
    )
    (net (code "67") (name "unconnected-(U1-IO15-Pad23)") (class "Default")
      (node (ref "U1") (pin "23") (pinfunction "IO15_23") (pintype "bidirectional"))
    )
    (net (code "68") (name "unconnected-(U1-IO23-Pad37)") (class "Default")
      (node (ref "U1") (pin "37") (pinfunction "IO23_37") (pintype "bidirectional"))
    )
    (net (code "69") (name "unconnected-(U1-IO25-Pad10)") (class "Default")
      (node (ref "U1") (pin "10") (pinfunction "IO25_10") (pintype "bidirectional"))
    )
    (net (code "70") (name "unconnected-(U1-IO26-Pad11)") (class "Default")
      (node (ref "U1") (pin "11") (pinfunction "IO26_11") (pintype "bidirectional"))
    )
    (net (code "71") (name "unconnected-(U1-IO27-Pad12)") (class "Default")
      (node (ref "U1") (pin "12") (pinfunction "IO27_12") (pintype "bidirectional"))
    )
    (net (code "72") (name "unconnected-(U1-IO32-Pad8)") (class "Default")
      (node (ref "U1") (pin "8") (pinfunction "IO32_8") (pintype "bidirectional"))
    )
    (net (code "73") (name "unconnected-(U1-IO33-Pad9)") (class "Default")
      (node (ref "U1") (pin "9") (pinfunction "IO33_9") (pintype "bidirectional"))
    )
    (net (code "74") (name "unconnected-(U1-IO34-Pad6)") (class "Default")
      (node (ref "U1") (pin "6") (pinfunction "IO34_6") (pintype "input+no_connect"))
    )
    (net (code "75") (name "unconnected-(U1-IO35-Pad7)") (class "Default")
      (node (ref "U1") (pin "7") (pinfunction "IO35_7") (pintype "input+no_connect"))
    )
    (net (code "76") (name "unconnected-(U1-NC-Pad32)") (class "Default")
      (node (ref "U1") (pin "32") (pinfunction "NC_32") (pintype "passive"))
    )
    (net (code "77") (name "unconnected-(U1-SCK{slash}CLK-Pad20)") (class "Default")
      (node (ref "U1") (pin "20") (pinfunction "SCK/CLK_20") (pintype "bidirectional"))
    )
    (net (code "78") (name "unconnected-(U1-SCS{slash}CMD-Pad19)") (class "Default")
      (node (ref "U1") (pin "19") (pinfunction "SCS/CMD_19") (pintype "bidirectional"))
    )
    (net (code "79") (name "unconnected-(U1-SDI{slash}SD1-Pad22)") (class "Default")
      (node (ref "U1") (pin "22") (pinfunction "SDI/SD1_22") (pintype "bidirectional"))
    )
    (net (code "80") (name "unconnected-(U1-SDO{slash}SD0-Pad21)") (class "Default")
      (node (ref "U1") (pin "21") (pinfunction "SDO/SD0_21") (pintype "bidirectional"))
    )
    (net (code "81") (name "unconnected-(U1-SENSOR_VN-Pad5)") (class "Default")
      (node (ref "U1") (pin "5") (pinfunction "SENSOR_VN_5") (pintype "input+no_connect"))
    )
    (net (code "82") (name "unconnected-(U1-SENSOR_VP-Pad4)") (class "Default")
      (node (ref "U1") (pin "4") (pinfunction "SENSOR_VP_4") (pintype "input+no_connect"))
    )
    (net (code "83") (name "unconnected-(U1-SHD{slash}SD2-Pad17)") (class "Default")
      (node (ref "U1") (pin "17") (pinfunction "SHD/SD2_17") (pintype "bidirectional"))
    )
    (net (code "84") (name "unconnected-(U1-SWP{slash}SD3-Pad18)") (class "Default")
      (node (ref "U1") (pin "18") (pinfunction "SWP/SD3_18") (pintype "bidirectional"))
    )
  )
)
